# EcobitNRF9160_EV2.net
KiCad netlist of a schematic drawn in EAGLE
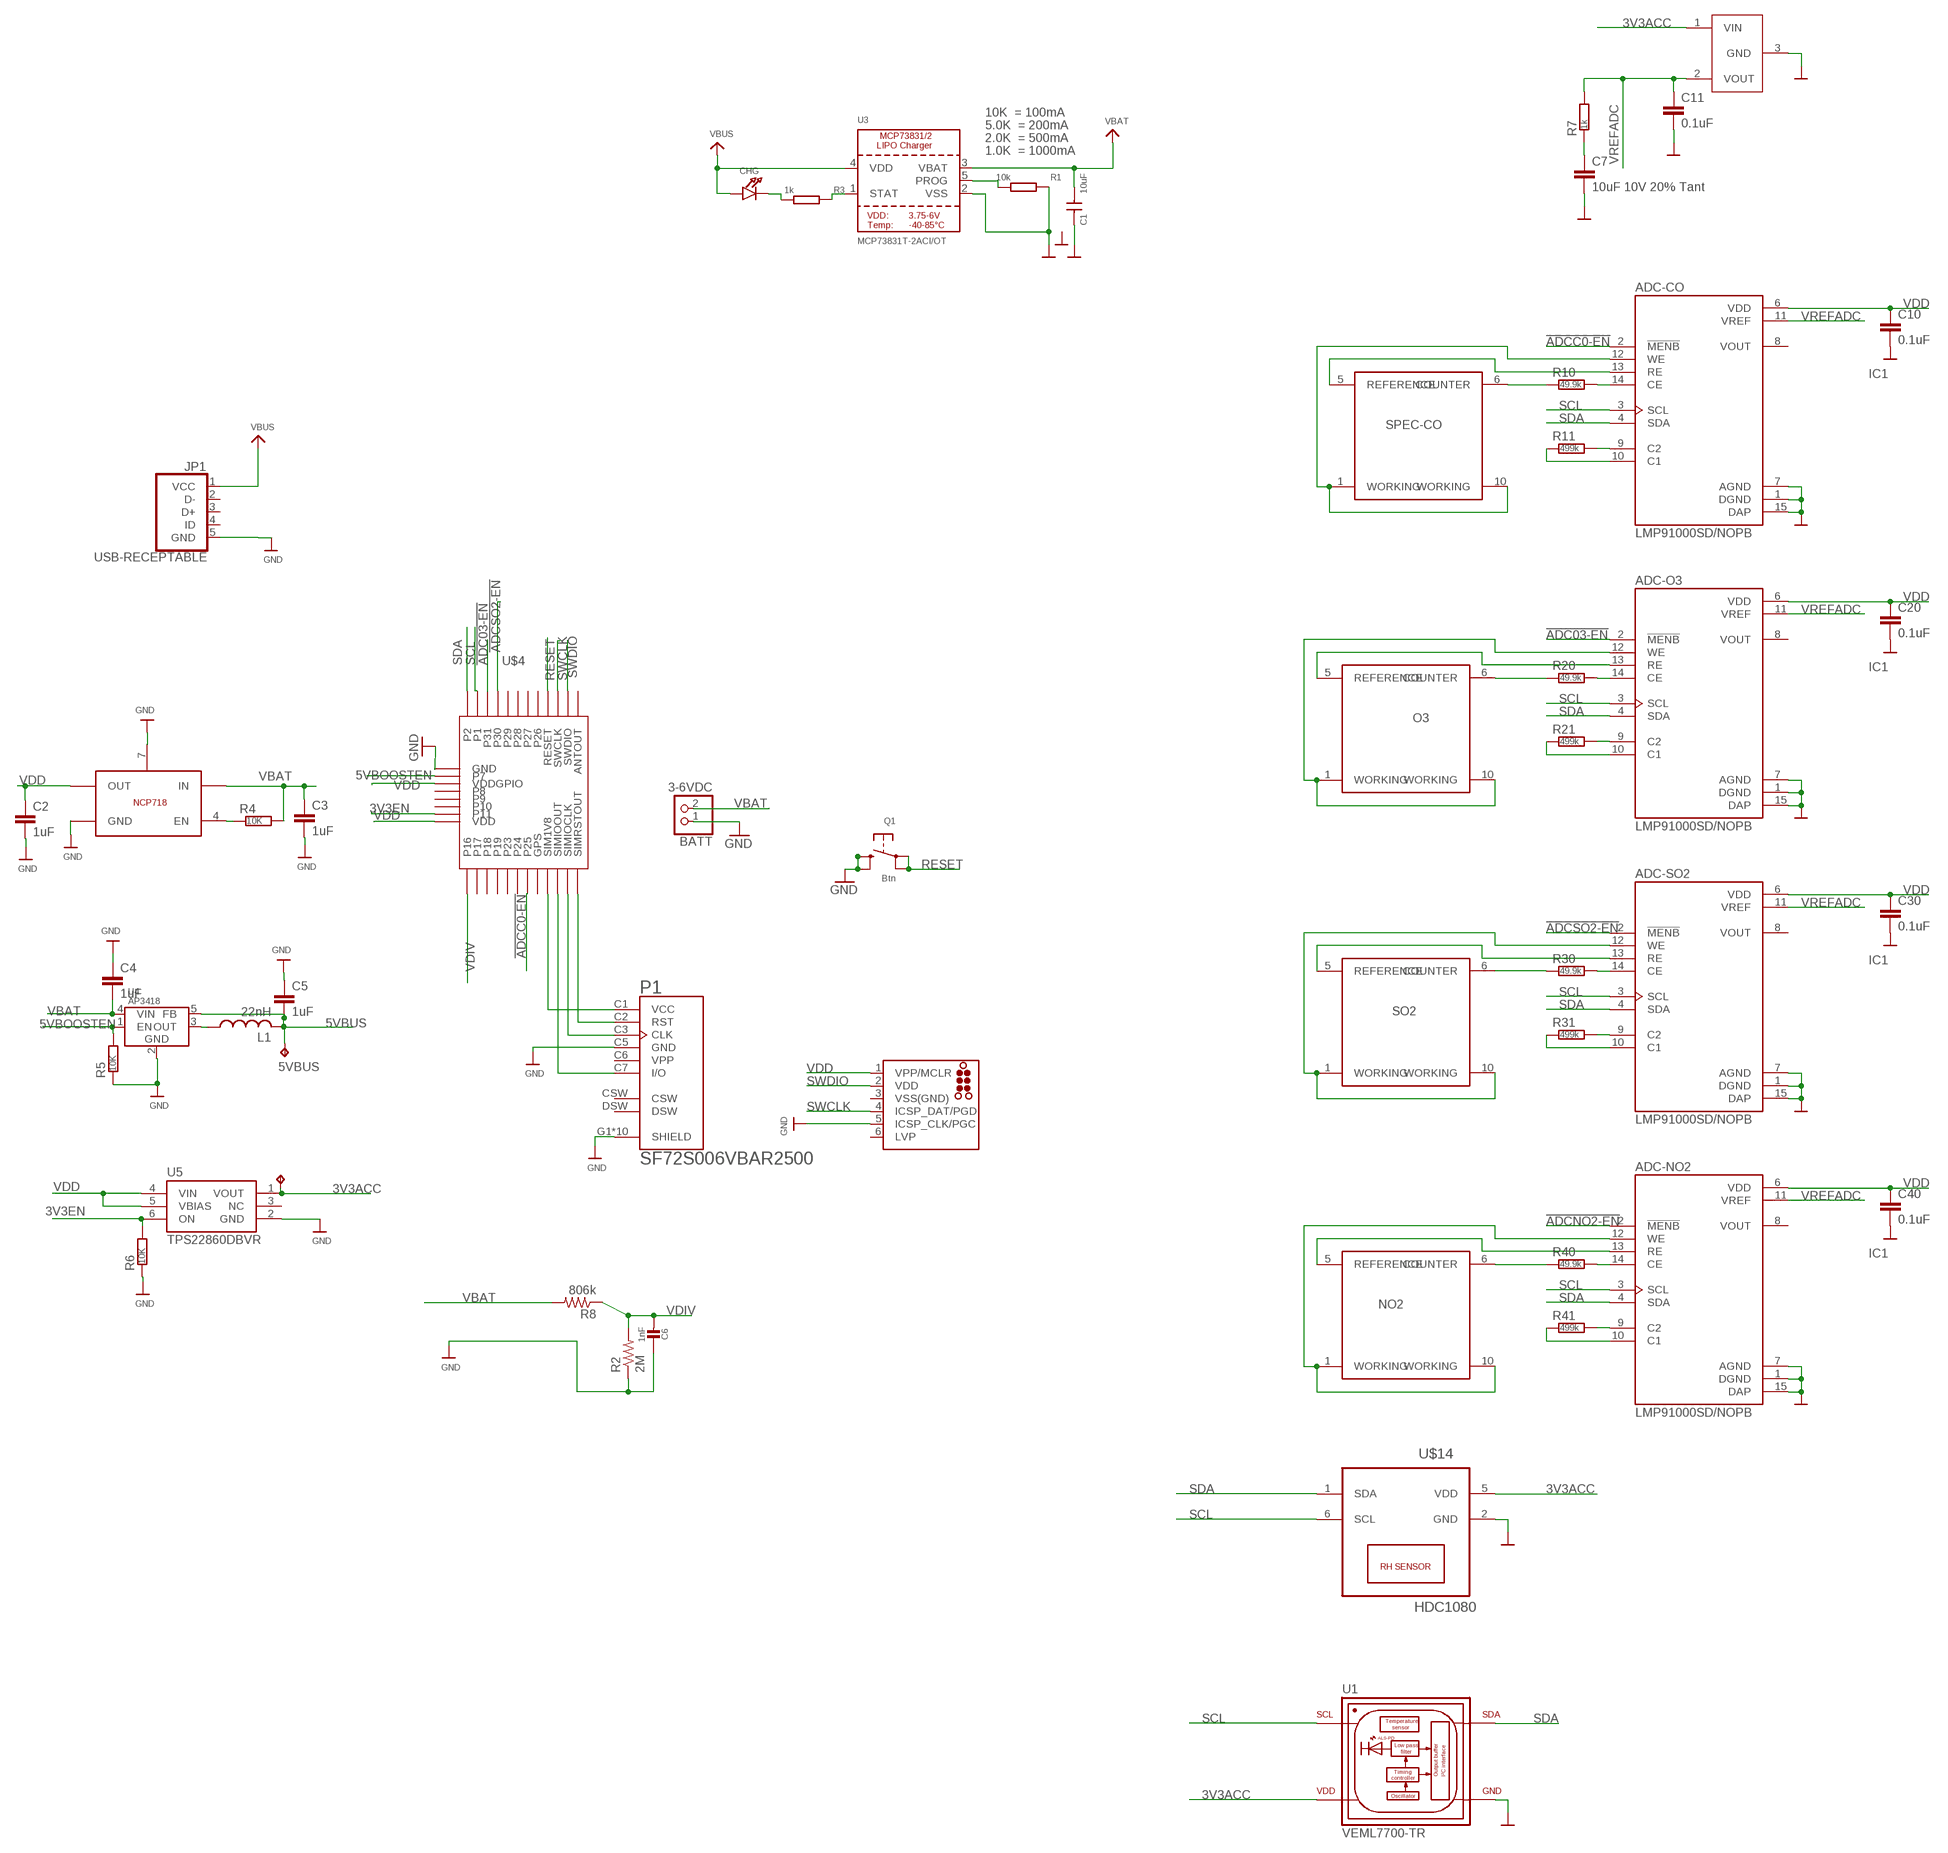
[diagram p0: schematic, sheet 1]

(export (version "E")
  (design (tool "Eeschema 10.0.6"))
  (components
    (comp (ref "5VBUS")
      (value "TPTP15R")
      (footprint "eagle-import:TP15R")
      (libsource (lib "eagle-import") (part "TPTP15R"))
    )
    (comp (ref "5VBUS1")
      (value "TPTP15R")
      (footprint "eagle-import:TP15R")
      (libsource (lib "eagle-import") (part "TPTP15R"))
    )
    (comp (ref "ADC-CO")
      (value "LMP91000SD/NOPB")
      (footprint "eagle-import:SON50P400X400X80-15N")
      (fields (field (name "MF") "Texas Instruments"))
      (libsource (lib "eagle-import") (part "LMP91000SD/NOPB"))
    )
    (comp (ref "ADC-NO2")
      (value "LMP91000SD/NOPB")
      (footprint "eagle-import:SON50P400X400X80-15N")
      (fields (field (name "MF") "Texas Instruments"))
      (libsource (lib "eagle-import") (part "LMP91000SD/NOPB"))
    )
    (comp (ref "ADC-O3")
      (value "LMP91000SD/NOPB")
      (footprint "eagle-import:SON50P400X400X80-15N")
      (fields (field (name "MF") "Texas Instruments"))
      (libsource (lib "eagle-import") (part "LMP91000SD/NOPB"))
    )
    (comp (ref "ADC-SO2")
      (value "LMP91000SD/NOPB")
      (footprint "eagle-import:SON50P400X400X80-15N")
      (fields (field (name "MF") "Texas Instruments"))
      (libsource (lib "eagle-import") (part "LMP91000SD/NOPB"))
    )
    (comp (ref "BATT")
      (value "3-6VDC")
      (footprint "eagle-import:JSTPH2")
      (libsource (lib "eagle-import") (part "CON_JST_PH_2PIN"))
    )
    (comp (ref "C1")
      (value "10uF")
      (footprint "eagle-import:C-0402")
      (libsource (lib "eagle-import") (part "CAP0402"))
    )
    (comp (ref "C2")
      (value "1uF")
      (footprint "eagle-import:RESC0402_N")
      (libsource (lib "eagle-import") (part "CAPACITOR_0402_N"))
    )
    (comp (ref "C3")
      (value "1uF")
      (footprint "eagle-import:RESC0402_N")
      (libsource (lib "eagle-import") (part "CAPACITOR_0402_N"))
    )
    (comp (ref "C4")
      (value "1uF")
      (footprint "eagle-import:RESC0402_N")
      (libsource (lib "eagle-import") (part "CAPACITOR_0402_N"))
    )
    (comp (ref "C5")
      (value "1uF")
      (footprint "eagle-import:RESC0402_N")
      (libsource (lib "eagle-import") (part "CAPACITOR_0402_N"))
    )
    (comp (ref "C6")
      (value "1nF")
      (footprint "eagle-import:0603-NO")
      (libsource (lib "eagle-import") (part "CAP_CERAMIC0603_NO"))
    )
    (comp (ref "C7")
      (value "10uF 10V 20% Tant")
      (footprint "eagle-import:RESC0805_N")
      (libsource (lib "eagle-import") (part "CAPACITOR_0805_N"))
    )
    (comp (ref "C10")
      (value "0.1uF")
      (footprint "eagle-import:RESC0603_N")
      (libsource (lib "eagle-import") (part "CAPACITOR_0603_N"))
    )
    (comp (ref "C11")
      (value "0.1uF")
      (footprint "eagle-import:RESC0603_N")
      (libsource (lib "eagle-import") (part "CAPACITOR_0603_N"))
    )
    (comp (ref "C20")
      (value "0.1uF")
      (footprint "eagle-import:RESC0603_N")
      (libsource (lib "eagle-import") (part "CAPACITOR_0603_N"))
    )
    (comp (ref "C30")
      (value "0.1uF")
      (footprint "eagle-import:RESC0603_N")
      (libsource (lib "eagle-import") (part "CAPACITOR_0603_N"))
    )
    (comp (ref "C40")
      (value "0.1uF")
      (footprint "eagle-import:RESC0603_N")
      (libsource (lib "eagle-import") (part "CAPACITOR_0603_N"))
    )
    (comp (ref "CHG")
      (value "LED0805_NOOUTLINE")
      (footprint "eagle-import:CHIPLED_0805_NOOUTLINE")
      (libsource (lib "eagle-import") (part "LED0805_NOOUTLINE"))
    )
    (comp (ref "IC1")
      (value "ISL60002DIH320Z-TK")
      (footprint "eagle-import:SOT-23-3")
      (libsource (lib "eagle-import") (part "ISL60002DIH320Z-TK"))
    )
    (comp (ref "J2")
      (value "TC2030-MCP-NL")
      (footprint "eagle-import:TC2030-MCP-NL")
      (libsource (lib "eagle-import") (part "TC2030-MCP-NL"))
    )
    (comp (ref "JP1")
      (value "USB-RECEPTABLE")
      (footprint "eagle-import:FCI-10103594-0001LF")
      (libsource (lib "eagle-import") (part "USB-RECEPTABLE"))
    )
    (comp (ref "L1")
      (value "22nH")
      (footprint "eagle-import:RESC0603_N")
      (libsource (lib "eagle-import") (part "INDUCTOR_0603_N"))
    )
    (comp (ref "NO2")
      (value "SPECSENSOR")
      (footprint "eagle-import:SPECSENSOR")
      (libsource (lib "eagle-import") (part "SPECSENSOR"))
    )
    (comp (ref "O3")
      (value "SPECSENSOR")
      (footprint "eagle-import:SPECSENSOR")
      (libsource (lib "eagle-import") (part "SPECSENSOR"))
    )
    (comp (ref "P1")
      (value "SF72S006VBAR2500")
      (footprint "eagle-import:JAE_SF72S006VBAR2500")
      (fields (field (name "MF") "JAE Electronics"))
      (libsource (lib "eagle-import") (part "SF72S006VBAR2500"))
    )
    (comp (ref "Q1")
      (value "Btn")
      (footprint "eagle-import:BTN_KMR2_4.6X2.8")
      (libsource (lib "eagle-import") (part "SWITCH_TACT_SMT4.6X2.8"))
    )
    (comp (ref "R1")
      (value "10k")
      (footprint "eagle-import:R0402")
      (libsource (lib "eagle-import") (part "RESR0402"))
    )
    (comp (ref "R2")
      (value "2M")
      (footprint "eagle-import:R0603")
      (libsource (lib "eagle-import") (part "R-US_R0603"))
    )
    (comp (ref "R3")
      (value "1k")
      (footprint "eagle-import:R0402")
      (libsource (lib "eagle-import") (part "RESR0402"))
    )
    (comp (ref "R4")
      (value "10K")
      (footprint "eagle-import:RESC0402_N")
      (libsource (lib "eagle-import") (part "RESISTOR_0402_N"))
    )
    (comp (ref "R5")
      (value "10K")
      (footprint "eagle-import:RESC0402_N")
      (libsource (lib "eagle-import") (part "RESISTOR_0402_N"))
    )
    (comp (ref "R6")
      (value "10K")
      (footprint "eagle-import:RESC0402_N")
      (libsource (lib "eagle-import") (part "RESISTOR_0402_N"))
    )
    (comp (ref "R7")
      (value "1k")
      (footprint "eagle-import:RESC0603_N")
      (libsource (lib "eagle-import") (part "RESISTOR_0603_N"))
    )
    (comp (ref "R8")
      (value "806k")
      (footprint "eagle-import:R0603")
      (libsource (lib "eagle-import") (part "R-US_R0603"))
    )
    (comp (ref "R10")
      (value "49.9k")
      (footprint "eagle-import:RESC0603_N")
      (libsource (lib "eagle-import") (part "RESISTOR_0603_N"))
    )
    (comp (ref "R11")
      (value "499k")
      (footprint "eagle-import:RESC0603_N")
      (libsource (lib "eagle-import") (part "RESISTOR_0603_N"))
    )
    (comp (ref "R20")
      (value "49.9k")
      (footprint "eagle-import:RESC0603_N")
      (libsource (lib "eagle-import") (part "RESISTOR_0603_N"))
    )
    (comp (ref "R21")
      (value "499k")
      (footprint "eagle-import:RESC0603_N")
      (libsource (lib "eagle-import") (part "RESISTOR_0603_N"))
    )
    (comp (ref "R30")
      (value "49.9k")
      (footprint "eagle-import:RESC0603_N")
      (libsource (lib "eagle-import") (part "RESISTOR_0603_N"))
    )
    (comp (ref "R31")
      (value "499k")
      (footprint "eagle-import:RESC0603_N")
      (libsource (lib "eagle-import") (part "RESISTOR_0603_N"))
    )
    (comp (ref "R40")
      (value "49.9k")
      (footprint "eagle-import:RESC0603_N")
      (libsource (lib "eagle-import") (part "RESISTOR_0603_N"))
    )
    (comp (ref "R41")
      (value "499k")
      (footprint "eagle-import:RESC0603_N")
      (libsource (lib "eagle-import") (part "RESISTOR_0603_N"))
    )
    (comp (ref "SO2")
      (value "SPECSENSOR")
      (footprint "eagle-import:SPECSENSOR")
      (libsource (lib "eagle-import") (part "SPECSENSOR"))
    )
    (comp (ref "SPEC-CO")
      (value "SPECSENSOR")
      (footprint "eagle-import:SPECSENSOR")
      (libsource (lib "eagle-import") (part "SPECSENSOR"))
    )
    (comp (ref "U$4")
      (value "NRF9160MODULE")
      (footprint "eagle-import:NRF9160MODULE")
      (libsource (lib "eagle-import") (part "NRF9160MODULE"))
    )
    (comp (ref "U$14")
      (value "HDC1080")
      (footprint "eagle-import:TI-S-PWSON-N6")
      (libsource (lib "eagle-import") (part "HDC1080"))
    )
    (comp (ref "U1")
      (value "VEML7700-TR")
      (footprint "eagle-import:XDCR_VEML7700-TR")
      (fields (field (name "DIGI-KEY_PART_NUMBER") "VEML7700CT-ND") (field (name "MF") "Vishay"))
      (libsource (lib "eagle-import") (part "VEML7700-TR"))
    )
    (comp (ref "U2")
      (value "NCP718")
      (footprint "eagle-import:NCP718-WDFN6")
      (libsource (lib "eagle-import") (part "NCP718"))
    )
    (comp (ref "U3")
      (value "MCP73831T-2ACI/OT")
      (footprint "eagle-import:SOT23-5")
      (libsource (lib "eagle-import") (part "MCP73831/2"))
    )
    (comp (ref "U4")
      (value "AP3418")
      (footprint "eagle-import:SOT25")
      (libsource (lib "eagle-import") (part "AP3418"))
    )
    (comp (ref "U5")
      (value "TPS22860DBVR")
      (footprint "eagle-import:R-PDSO-G6")
      (libsource (lib "eagle-import") (part "TPS22860DBVR"))
    )
  )
  (nets
    (net (code "1") (name "/3V3ACC") (class "Default")
      (node (ref "5VBUS1") (pin "TP") (pinfunction "TP_TP") (pintype "input"))
      (node (ref "IC1") (pin "1") (pinfunction "VIN_1") (pintype "power_in"))
      (node (ref "U$14") (pin "5") (pinfunction "VDD_5") (pintype "output"))
      (node (ref "U1") (pin "2") (pinfunction "VDD_2") (pintype "power_in"))
      (node (ref "U5") (pin "1") (pinfunction "VOUT_1") (pintype "power_in"))
    )
    (net (code "2") (name "/3V3EN") (class "Default")
      (node (ref "R6") (pin "2") (pinfunction "2_2") (pintype "passive"))
      (node (ref "U$4") (pin "P11") (pinfunction "P11_P11") (pintype "bidirectional"))
      (node (ref "U5") (pin "6") (pinfunction "ON_6") (pintype "input"))
    )
    (net (code "3") (name "/5VBOOSTEN") (class "Default")
      (node (ref "R5") (pin "2") (pinfunction "2_2") (pintype "passive"))
      (node (ref "U$4") (pin "P7") (pinfunction "P7_P7") (pintype "bidirectional"))
      (node (ref "U4") (pin "1") (pinfunction "EN_1") (pintype "bidirectional"))
    )
    (net (code "4") (name "/5VBUS") (class "Default")
      (node (ref "5VBUS") (pin "TP") (pinfunction "TP_TP") (pintype "input"))
      (node (ref "C5") (pin "2") (pinfunction "2_2") (pintype "passive"))
      (node (ref "L1") (pin "2") (pinfunction "2_2") (pintype "passive"))
      (node (ref "U4") (pin "5") (pinfunction "FB_5") (pintype "bidirectional"))
    )
    (net (code "8") (name "/RESET") (class "Default")
      (node (ref "Q1") (pin "A") (pinfunction "P_A") (pintype "passive"))
      (node (ref "Q1") (pin "A'") (pinfunction "P1_A'") (pintype "passive"))
      (node (ref "U$4") (pin "RESET") (pinfunction "RESET_RESET") (pintype "bidirectional"))
    )
    (net (code "9") (name "/SCL") (class "Default")
      (node (ref "ADC-CO") (pin "3") (pinfunction "SCL_3") (pintype "input"))
      (node (ref "ADC-NO2") (pin "3") (pinfunction "SCL_3") (pintype "input"))
      (node (ref "ADC-O3") (pin "3") (pinfunction "SCL_3") (pintype "input"))
      (node (ref "ADC-SO2") (pin "3") (pinfunction "SCL_3") (pintype "input"))
      (node (ref "U$14") (pin "6") (pinfunction "SCL_6") (pintype "passive"))
      (node (ref "U$4") (pin "P1") (pinfunction "P1_P1") (pintype "bidirectional"))
      (node (ref "U1") (pin "1") (pinfunction "SCL_1") (pintype "input"))
    )
    (net (code "10") (name "/SDA") (class "Default")
      (node (ref "ADC-CO") (pin "4") (pinfunction "SDA_4") (pintype "bidirectional"))
      (node (ref "ADC-NO2") (pin "4") (pinfunction "SDA_4") (pintype "bidirectional"))
      (node (ref "ADC-O3") (pin "4") (pinfunction "SDA_4") (pintype "bidirectional"))
      (node (ref "ADC-SO2") (pin "4") (pinfunction "SDA_4") (pintype "bidirectional"))
      (node (ref "U$14") (pin "1") (pinfunction "SDA_1") (pintype "power_in"))
      (node (ref "U$4") (pin "P2") (pinfunction "P2_P2") (pintype "bidirectional"))
      (node (ref "U1") (pin "4") (pinfunction "SDA_4") (pintype "bidirectional"))
    )
    (net (code "13") (name "/SWCLK") (class "Default")
      (node (ref "J2") (pin "4") (pinfunction "ICSP_DAT/PGD_4") (pintype "bidirectional"))
      (node (ref "U$4") (pin "SWCLK") (pinfunction "SWCLK_SWCLK") (pintype "bidirectional"))
    )
    (net (code "14") (name "/SWDIO") (class "Default")
      (node (ref "J2") (pin "2") (pinfunction "VDD_2") (pintype "power_in"))
      (node (ref "U$4") (pin "SWDIO") (pinfunction "SWDIO_SWDIO") (pintype "bidirectional"))
    )
    (net (code "15") (name "/VDD") (class "Default")
      (node (ref "ADC-CO") (pin "6") (pinfunction "VDD_6") (pintype "power_in"))
      (node (ref "ADC-NO2") (pin "6") (pinfunction "VDD_6") (pintype "power_in"))
      (node (ref "ADC-O3") (pin "6") (pinfunction "VDD_6") (pintype "power_in"))
      (node (ref "ADC-SO2") (pin "6") (pinfunction "VDD_6") (pintype "power_in"))
      (node (ref "C10") (pin "1") (pinfunction "1_1") (pintype "passive"))
      (node (ref "C2") (pin "1") (pinfunction "1_1") (pintype "passive"))
      (node (ref "C20") (pin "1") (pinfunction "1_1") (pintype "passive"))
      (node (ref "C30") (pin "1") (pinfunction "1_1") (pintype "passive"))
      (node (ref "C40") (pin "1") (pinfunction "1_1") (pintype "passive"))
      (node (ref "J2") (pin "1") (pinfunction "VPP/MCLR_1") (pintype "passive"))
      (node (ref "U$4") (pin "VDD") (pinfunction "VDD_VDD") (pintype "bidirectional"))
      (node (ref "U$4") (pin "VDDGPIO") (pinfunction "VDDGPIO_VDDGPIO") (pintype "bidirectional"))
      (node (ref "U2") (pin "1") (pinfunction "OUT_1") (pintype "power_in"))
      (node (ref "U5") (pin "4") (pinfunction "VIN_4") (pintype "power_in"))
      (node (ref "U5") (pin "5") (pinfunction "VBIAS_5") (pintype "power_in"))
    )
    (net (code "16") (name "/VDIV") (class "Default")
      (node (ref "C6") (pin "2") (pinfunction "2_2") (pintype "passive"))
      (node (ref "R2") (pin "2") (pinfunction "2_2") (pintype "passive"))
      (node (ref "R8") (pin "1") (pinfunction "1_1") (pintype "passive"))
      (node (ref "U$4") (pin "P16") (pinfunction "P16_P16") (pintype "bidirectional"))
    )
    (net (code "17") (name "/VPP") (class "Default")
      (node (ref "P1") (pin "C6") (pinfunction "VPP_C6") (pintype "power_in"))
    )
    (net (code "18") (name "/VREFADC") (class "Default")
      (node (ref "ADC-CO") (pin "11") (pinfunction "VREF_11") (pintype "power_in"))
      (node (ref "ADC-NO2") (pin "11") (pinfunction "VREF_11") (pintype "power_in"))
      (node (ref "ADC-O3") (pin "11") (pinfunction "VREF_11") (pintype "power_in"))
      (node (ref "ADC-SO2") (pin "11") (pinfunction "VREF_11") (pintype "power_in"))
      (node (ref "C11") (pin "1") (pinfunction "1_1") (pintype "passive"))
      (node (ref "IC1") (pin "2") (pinfunction "VOUT_2") (pintype "power_in"))
      (node (ref "R7") (pin "2") (pinfunction "2_2") (pintype "passive"))
    )
    (net (code "19") (name "/VSS(GND)") (class "Default")
      (node (ref "J2") (pin "3") (pinfunction "VSS(GND)_3") (pintype "power_in"))
    )
    (net (code "20") (name "/~{ADC03-EN}") (class "Default")
      (node (ref "ADC-O3") (pin "2") (pinfunction "~{MENB}_2") (pintype "input"))
      (node (ref "U$4") (pin "P31") (pinfunction "P31_P31") (pintype "bidirectional"))
    )
    (net (code "21") (name "/~{ADCC0-EN}") (class "Default")
      (node (ref "ADC-CO") (pin "2") (pinfunction "~{MENB}_2") (pintype "input"))
      (node (ref "U$4") (pin "P25") (pinfunction "P25_P25") (pintype "bidirectional"))
    )
    (net (code "22") (name "/~{ADCNO2-EN}") (class "Default")
      (node (ref "ADC-NO2") (pin "2") (pinfunction "~{MENB}_2") (pintype "input"))
    )
    (net (code "23") (name "/~{ADCSO2-EN}") (class "Default")
      (node (ref "ADC-SO2") (pin "2") (pinfunction "~{MENB}_2") (pintype "input"))
      (node (ref "U$4") (pin "P30") (pinfunction "P30_P30") (pintype "bidirectional"))
    )
    (net (code "24") (name "GND") (class "Default")
      (node (ref "ADC-CO") (pin "1") (pinfunction "DGND_1") (pintype "power_in"))
      (node (ref "ADC-CO") (pin "15") (pinfunction "DAP_15") (pintype "power_in"))
      (node (ref "ADC-CO") (pin "7") (pinfunction "AGND_7") (pintype "power_in"))
      (node (ref "ADC-NO2") (pin "1") (pinfunction "DGND_1") (pintype "power_in"))
      (node (ref "ADC-NO2") (pin "15") (pinfunction "DAP_15") (pintype "power_in"))
      (node (ref "ADC-NO2") (pin "7") (pinfunction "AGND_7") (pintype "power_in"))
      (node (ref "ADC-O3") (pin "1") (pinfunction "DGND_1") (pintype "power_in"))
      (node (ref "ADC-O3") (pin "15") (pinfunction "DAP_15") (pintype "power_in"))
      (node (ref "ADC-O3") (pin "7") (pinfunction "AGND_7") (pintype "power_in"))
      (node (ref "ADC-SO2") (pin "1") (pinfunction "DGND_1") (pintype "power_in"))
      (node (ref "ADC-SO2") (pin "15") (pinfunction "DAP_15") (pintype "power_in"))
      (node (ref "ADC-SO2") (pin "7") (pinfunction "AGND_7") (pintype "power_in"))
      (node (ref "BATT") (pin "1") (pinfunction "1_1") (pintype "passive"))
      (node (ref "C1") (pin "2") (pinfunction "2_2") (pintype "bidirectional"))
      (node (ref "C10") (pin "2") (pinfunction "2_2") (pintype "passive"))
      (node (ref "C11") (pin "2") (pinfunction "2_2") (pintype "passive"))
      (node (ref "C2") (pin "2") (pinfunction "2_2") (pintype "passive"))
      (node (ref "C20") (pin "2") (pinfunction "2_2") (pintype "passive"))
      (node (ref "C3") (pin "2") (pinfunction "2_2") (pintype "passive"))
      (node (ref "C30") (pin "2") (pinfunction "2_2") (pintype "passive"))
      (node (ref "C4") (pin "1") (pinfunction "1_1") (pintype "passive"))
      (node (ref "C40") (pin "2") (pinfunction "2_2") (pintype "passive"))
      (node (ref "C5") (pin "1") (pinfunction "1_1") (pintype "passive"))
      (node (ref "C6") (pin "1") (pinfunction "1_1") (pintype "passive"))
      (node (ref "C7") (pin "2") (pinfunction "2_2") (pintype "passive"))
      (node (ref "IC1") (pin "3") (pinfunction "GND_3") (pintype "power_in"))
      (node (ref "J2") (pin "5") (pinfunction "ICSP_CLK/PGC_5") (pintype "output"))
      (node (ref "JP1") (pin "5") (pinfunction "GND_5") (pintype "bidirectional"))
      (node (ref "P1") (pin "C5") (pinfunction "GND_C5") (pintype "power_in"))
      (node (ref "P1") (pin "G1") (pinfunction "SHIELD_G1") (pintype "passive"))
      (node (ref "P1") (pin "G10") (pinfunction "SHIELD_G10") (pintype "passive"))
      (node (ref "P1") (pin "G2") (pinfunction "SHIELD_G2") (pintype "passive"))
      (node (ref "P1") (pin "G3") (pinfunction "SHIELD_G3") (pintype "passive"))
      (node (ref "P1") (pin "G4") (pinfunction "SHIELD_G4") (pintype "passive"))
      (node (ref "P1") (pin "G5") (pinfunction "SHIELD_G5") (pintype "passive"))
      (node (ref "P1") (pin "G6") (pinfunction "SHIELD_G6") (pintype "passive"))
      (node (ref "P1") (pin "G7") (pinfunction "SHIELD_G7") (pintype "passive"))
      (node (ref "P1") (pin "G8") (pinfunction "SHIELD_G8") (pintype "passive"))
      (node (ref "P1") (pin "G9") (pinfunction "SHIELD_G9") (pintype "passive"))
      (node (ref "Q1") (pin "B") (pinfunction "S_B") (pintype "passive"))
      (node (ref "Q1") (pin "B'") (pinfunction "S1_B'") (pintype "passive"))
      (node (ref "R1") (pin "1") (pinfunction "1_1") (pintype "bidirectional"))
      (node (ref "R2") (pin "1") (pinfunction "1_1") (pintype "passive"))
      (node (ref "R5") (pin "1") (pinfunction "1_1") (pintype "passive"))
      (node (ref "R6") (pin "1") (pinfunction "1_1") (pintype "passive"))
      (node (ref "U$14") (pin "2") (pinfunction "GND_2") (pintype "passive"))
      (node (ref "U$4") (pin "GND") (pinfunction "GND_GND") (pintype "bidirectional"))
      (node (ref "U1") (pin "3") (pinfunction "GND_3") (pintype "power_in"))
      (node (ref "U2") (pin "3") (pinfunction "GND_3") (pintype "power_in"))
      (node (ref "U2") (pin "7") (pinfunction "GND_7") (pintype "power_in"))
      (node (ref "U3") (pin "2") (pinfunction "VSS_2") (pintype "power_in"))
      (node (ref "U4") (pin "2") (pinfunction "GND_2") (pintype "bidirectional"))
      (node (ref "U5") (pin "2") (pinfunction "GND_2") (pintype "power_in"))
    )
    (net (code "25") (name "Net-(ADC-CO-C1)") (class "Default")
      (node (ref "ADC-CO") (pin "10") (pinfunction "C1_10") (pintype "passive"))
      (node (ref "R11") (pin "1") (pinfunction "1_1") (pintype "passive"))
    )
    (net (code "26") (name "Net-(ADC-CO-C2)") (class "Default")
      (node (ref "ADC-CO") (pin "9") (pinfunction "C2_9") (pintype "passive"))
      (node (ref "R11") (pin "2") (pinfunction "2_2") (pintype "passive"))
    )
    (net (code "27") (name "Net-(ADC-CO-CE)") (class "Default")
      (node (ref "ADC-CO") (pin "14") (pinfunction "CE_14") (pintype "input"))
      (node (ref "R10") (pin "2") (pinfunction "2_2") (pintype "passive"))
    )
    (net (code "28") (name "Net-(ADC-CO-RE)") (class "Default")
      (node (ref "ADC-CO") (pin "13") (pinfunction "RE_13") (pintype "input"))
      (node (ref "SPEC-CO") (pin "5") (pinfunction "REFERENCE_5") (pintype "bidirectional"))
    )
    (net (code "29") (name "Net-(ADC-CO-WE)") (class "Default")
      (node (ref "ADC-CO") (pin "12") (pinfunction "WE_12") (pintype "input"))
      (node (ref "SPEC-CO") (pin "1") (pinfunction "WORKING_1") (pintype "bidirectional"))
      (node (ref "SPEC-CO") (pin "10") (pinfunction "WORKING_10") (pintype "bidirectional"))
    )
    (net (code "30") (name "Net-(ADC-NO2-C1)") (class "Default")
      (node (ref "ADC-NO2") (pin "10") (pinfunction "C1_10") (pintype "passive"))
      (node (ref "R41") (pin "1") (pinfunction "1_1") (pintype "passive"))
    )
    (net (code "31") (name "Net-(ADC-NO2-C2)") (class "Default")
      (node (ref "ADC-NO2") (pin "9") (pinfunction "C2_9") (pintype "passive"))
      (node (ref "R41") (pin "2") (pinfunction "2_2") (pintype "passive"))
    )
    (net (code "32") (name "Net-(ADC-NO2-CE)") (class "Default")
      (node (ref "ADC-NO2") (pin "14") (pinfunction "CE_14") (pintype "input"))
      (node (ref "R40") (pin "2") (pinfunction "2_2") (pintype "passive"))
    )
    (net (code "33") (name "Net-(ADC-NO2-RE)") (class "Default")
      (node (ref "ADC-NO2") (pin "13") (pinfunction "RE_13") (pintype "input"))
      (node (ref "NO2") (pin "5") (pinfunction "REFERENCE_5") (pintype "bidirectional"))
    )
    (net (code "34") (name "Net-(ADC-NO2-WE)") (class "Default")
      (node (ref "ADC-NO2") (pin "12") (pinfunction "WE_12") (pintype "input"))
      (node (ref "NO2") (pin "1") (pinfunction "WORKING_1") (pintype "bidirectional"))
      (node (ref "NO2") (pin "10") (pinfunction "WORKING_10") (pintype "bidirectional"))
    )
    (net (code "35") (name "Net-(ADC-O3-C1)") (class "Default")
      (node (ref "ADC-O3") (pin "10") (pinfunction "C1_10") (pintype "passive"))
      (node (ref "R21") (pin "1") (pinfunction "1_1") (pintype "passive"))
    )
    (net (code "36") (name "Net-(ADC-O3-C2)") (class "Default")
      (node (ref "ADC-O3") (pin "9") (pinfunction "C2_9") (pintype "passive"))
      (node (ref "R21") (pin "2") (pinfunction "2_2") (pintype "passive"))
    )
    (net (code "37") (name "Net-(ADC-O3-CE)") (class "Default")
      (node (ref "ADC-O3") (pin "14") (pinfunction "CE_14") (pintype "input"))
      (node (ref "R20") (pin "2") (pinfunction "2_2") (pintype "passive"))
    )
    (net (code "38") (name "Net-(ADC-O3-RE)") (class "Default")
      (node (ref "ADC-O3") (pin "13") (pinfunction "RE_13") (pintype "input"))
      (node (ref "O3") (pin "5") (pinfunction "REFERENCE_5") (pintype "bidirectional"))
    )
    (net (code "39") (name "Net-(ADC-O3-WE)") (class "Default")
      (node (ref "ADC-O3") (pin "12") (pinfunction "WE_12") (pintype "input"))
      (node (ref "O3") (pin "1") (pinfunction "WORKING_1") (pintype "bidirectional"))
      (node (ref "O3") (pin "10") (pinfunction "WORKING_10") (pintype "bidirectional"))
    )
    (net (code "40") (name "Net-(ADC-SO2-C1)") (class "Default")
      (node (ref "ADC-SO2") (pin "10") (pinfunction "C1_10") (pintype "passive"))
      (node (ref "R31") (pin "1") (pinfunction "1_1") (pintype "passive"))
    )
    (net (code "41") (name "Net-(ADC-SO2-C2)") (class "Default")
      (node (ref "ADC-SO2") (pin "9") (pinfunction "C2_9") (pintype "passive"))
      (node (ref "R31") (pin "2") (pinfunction "2_2") (pintype "passive"))
    )
    (net (code "42") (name "Net-(ADC-SO2-CE)") (class "Default")
      (node (ref "ADC-SO2") (pin "14") (pinfunction "CE_14") (pintype "input"))
      (node (ref "R30") (pin "2") (pinfunction "2_2") (pintype "passive"))
    )
    (net (code "43") (name "Net-(ADC-SO2-RE)") (class "Default")
      (node (ref "ADC-SO2") (pin "13") (pinfunction "RE_13") (pintype "input"))
      (node (ref "SO2") (pin "5") (pinfunction "REFERENCE_5") (pintype "bidirectional"))
    )
    (net (code "44") (name "Net-(ADC-SO2-WE)") (class "Default")
      (node (ref "ADC-SO2") (pin "12") (pinfunction "WE_12") (pintype "input"))
      (node (ref "SO2") (pin "1") (pinfunction "WORKING_1") (pintype "bidirectional"))
      (node (ref "SO2") (pin "10") (pinfunction "WORKING_10") (pintype "bidirectional"))
    )
    (net (code "45") (name "Net-(C7-Pad1)") (class "Default")
      (node (ref "C7") (pin "1") (pinfunction "1_1") (pintype "passive"))
      (node (ref "R7") (pin "1") (pinfunction "1_1") (pintype "passive"))
    )
    (net (code "46") (name "Net-(CHG-PadC)") (class "Default")
      (node (ref "CHG") (pin "C") (pinfunction "C_C") (pintype "passive"))
      (node (ref "R3") (pin "2") (pinfunction "2_2") (pintype "bidirectional"))
    )
    (net (code "47") (name "Net-(NO2-COUNTER)") (class "Default")
      (node (ref "NO2") (pin "6") (pinfunction "COUNTER_6") (pintype "bidirectional"))
      (node (ref "R40") (pin "1") (pinfunction "1_1") (pintype "passive"))
    )
    (net (code "48") (name "Net-(O3-COUNTER)") (class "Default")
      (node (ref "O3") (pin "6") (pinfunction "COUNTER_6") (pintype "bidirectional"))
      (node (ref "R20") (pin "1") (pinfunction "1_1") (pintype "passive"))
    )
    (net (code "49") (name "Net-(P1-CLK)") (class "Default")
      (node (ref "P1") (pin "C3") (pinfunction "CLK_C3") (pintype "bidirectional"))
      (node (ref "U$4") (pin "SIMCLKOUT") (pinfunction "SIMIOCLK_SIMCLKOUT") (pintype "bidirectional"))
    )
    (net (code "50") (name "Net-(P1-I{slash}O)") (class "Default")
      (node (ref "P1") (pin "C7") (pinfunction "I/O_C7") (pintype "bidirectional"))
      (node (ref "U$4") (pin "SIMIOOUT") (pinfunction "SIMIOOUT_SIMIOOUT") (pintype "bidirectional"))
    )
    (net (code "51") (name "Net-(P1-RST)") (class "Default")
      (node (ref "P1") (pin "C2") (pinfunction "RST_C2") (pintype "bidirectional"))
      (node (ref "U$4") (pin "SIMRSTOUT") (pinfunction "SIMRSTOUT_SIMRSTOUT") (pintype "bidirectional"))
    )
    (net (code "52") (name "Net-(P1-VCC)") (class "Default")
      (node (ref "P1") (pin "C1") (pinfunction "VCC_C1") (pintype "power_in"))
      (node (ref "U$4") (pin "SIM1V8") (pinfunction "SIM1V8_SIM1V8") (pintype "bidirectional"))
    )
    (net (code "53") (name "Net-(SO2-COUNTER)") (class "Default")
      (node (ref "R30") (pin "1") (pinfunction "1_1") (pintype "passive"))
      (node (ref "SO2") (pin "6") (pinfunction "COUNTER_6") (pintype "bidirectional"))
    )
    (net (code "54") (name "Net-(SPEC-CO-COUNTER)") (class "Default")
      (node (ref "R10") (pin "1") (pinfunction "1_1") (pintype "passive"))
      (node (ref "SPEC-CO") (pin "6") (pinfunction "COUNTER_6") (pintype "bidirectional"))
    )
    (net (code "55") (name "Net-(U2-EN)") (class "Default")
      (node (ref "R4") (pin "1") (pinfunction "1_1") (pintype "passive"))
      (node (ref "U2") (pin "4") (pinfunction "EN_4") (pintype "bidirectional"))
    )
    (net (code "56") (name "Net-(U3-PROG)") (class "Default")
      (node (ref "R1") (pin "2") (pinfunction "2_2") (pintype "bidirectional"))
      (node (ref "U3") (pin "5") (pinfunction "PROG_5") (pintype "input"))
    )
    (net (code "57") (name "Net-(U3-STAT)") (class "Default")
      (node (ref "R3") (pin "1") (pinfunction "1_1") (pintype "bidirectional"))
      (node (ref "U3") (pin "1") (pinfunction "STAT_1") (pintype "output"))
    )
    (net (code "58") (name "Net-(U4-OUT)") (class "Default")
      (node (ref "L1") (pin "1") (pinfunction "1_1") (pintype "passive"))
      (node (ref "U4") (pin "3") (pinfunction "OUT_3") (pintype "bidirectional"))
    )
    (net (code "59") (name "VBAT") (class "Default")
      (node (ref "BATT") (pin "2") (pinfunction "2_2") (pintype "passive"))
      (node (ref "C1") (pin "1") (pinfunction "1_1") (pintype "bidirectional"))
      (node (ref "C3") (pin "1") (pinfunction "1_1") (pintype "passive"))
      (node (ref "C4") (pin "2") (pinfunction "2_2") (pintype "passive"))
      (node (ref "R4") (pin "2") (pinfunction "2_2") (pintype "passive"))
      (node (ref "R8") (pin "2") (pinfunction "2_2") (pintype "passive"))
      (node (ref "U2") (pin "6") (pinfunction "IN_6") (pintype "power_in"))
      (node (ref "U3") (pin "3") (pinfunction "VBAT_3") (pintype "power_in"))
      (node (ref "U4") (pin "4") (pinfunction "VIN_4") (pintype "bidirectional"))
    )
    (net (code "60") (name "VBUS") (class "Default")
      (node (ref "CHG") (pin "A") (pinfunction "A_A") (pintype "passive"))
      (node (ref "JP1") (pin "1") (pinfunction "VCC_1") (pintype "bidirectional"))
      (node (ref "U3") (pin "4") (pinfunction "VDD_4") (pintype "power_in"))
    )
    (net (code "61") (name "unconnected-(ADC-CO-VOUT-Pad8)") (class "Default")
      (node (ref "ADC-CO") (pin "8") (pinfunction "VOUT_8") (pintype "output"))
    )
    (net (code "62") (name "unconnected-(ADC-NO2-VOUT-Pad8)") (class "Default")
      (node (ref "ADC-NO2") (pin "8") (pinfunction "VOUT_8") (pintype "output"))
    )
    (net (code "63") (name "unconnected-(ADC-O3-VOUT-Pad8)") (class "Default")
      (node (ref "ADC-O3") (pin "8") (pinfunction "VOUT_8") (pintype "output"))
    )
    (net (code "64") (name "unconnected-(ADC-SO2-VOUT-Pad8)") (class "Default")
      (node (ref "ADC-SO2") (pin "8") (pinfunction "VOUT_8") (pintype "output"))
    )
    (net (code "65") (name "unconnected-(J2-LVP-Pad6)") (class "Default")
      (node (ref "J2") (pin "6") (pinfunction "LVP_6") (pintype "bidirectional"))
    )
    (net (code "66") (name "unconnected-(JP1-D+-Pad3)") (class "Default")
      (node (ref "JP1") (pin "3") (pinfunction "D+_3") (pintype "bidirectional"))
    )
    (net (code "67") (name "unconnected-(JP1-D--Pad2)") (class "Default")
      (node (ref "JP1") (pin "2") (pinfunction "D-_2") (pintype "bidirectional"))
    )
    (net (code "68") (name "unconnected-(JP1-ID-Pad4)") (class "Default")
      (node (ref "JP1") (pin "4") (pinfunction "ID_4") (pintype "bidirectional"))
    )
    (net (code "69") (name "unconnected-(P1-PadCSW)") (class "Default")
      (node (ref "P1") (pin "CSW") (pinfunction "CSW_CSW") (pintype "bidirectional"))
    )
    (net (code "70") (name "unconnected-(P1-PadDSW)") (class "Default")
      (node (ref "P1") (pin "DSW") (pinfunction "DSW_DSW") (pintype "bidirectional"))
    )
    (net (code "71") (name "unconnected-(U$4-PadANTOUT)") (class "Default")
      (node (ref "U$4") (pin "ANTOUT") (pinfunction "ANTOUT_ANTOUT") (pintype "bidirectional"))
    )
    (net (code "72") (name "unconnected-(U$4-PadGPS)") (class "Default")
      (node (ref "U$4") (pin "GPS") (pinfunction "GPS_GPS") (pintype "bidirectional"))
    )
    (net (code "73") (name "unconnected-(U$4-PadP8)") (class "Default")
      (node (ref "U$4") (pin "P8") (pinfunction "P8_P8") (pintype "bidirectional"))
    )
    (net (code "74") (name "unconnected-(U$4-PadP9)") (class "Default")
      (node (ref "U$4") (pin "P9") (pinfunction "P9_P9") (pintype "bidirectional"))
    )
    (net (code "75") (name "unconnected-(U$4-PadP10)") (class "Default")
      (node (ref "U$4") (pin "P10") (pinfunction "P10_P10") (pintype "bidirectional"))
    )
    (net (code "76") (name "unconnected-(U$4-PadP17)") (class "Default")
      (node (ref "U$4") (pin "P17") (pinfunction "P17_P17") (pintype "bidirectional"))
    )
    (net (code "77") (name "unconnected-(U$4-PadP18)") (class "Default")
      (node (ref "U$4") (pin "P18") (pinfunction "P18_P18") (pintype "bidirectional"))
    )
    (net (code "78") (name "unconnected-(U$4-PadP19)") (class "Default")
      (node (ref "U$4") (pin "P19") (pinfunction "P19_P19") (pintype "bidirectional"))
    )
    (net (code "79") (name "unconnected-(U$4-PadP23)") (class "Default")
      (node (ref "U$4") (pin "P23") (pinfunction "P23_P23") (pintype "bidirectional"))
    )
    (net (code "80") (name "unconnected-(U$4-PadP24)") (class "Default")
      (node (ref "U$4") (pin "P24") (pinfunction "P24_P24") (pintype "bidirectional"))
    )
    (net (code "81") (name "unconnected-(U$4-PadP26)") (class "Default")
      (node (ref "U$4") (pin "P26") (pinfunction "P26_P26") (pintype "bidirectional"))
    )
    (net (code "82") (name "unconnected-(U$4-PadP27)") (class "Default")
      (node (ref "U$4") (pin "P27") (pinfunction "P27_P27") (pintype "bidirectional"))
    )
    (net (code "83") (name "unconnected-(U$4-PadP28)") (class "Default")
      (node (ref "U$4") (pin "P28") (pinfunction "P28_P28") (pintype "bidirectional"))
    )
    (net (code "84") (name "unconnected-(U$4-PadP29)") (class "Default")
      (node (ref "U$4") (pin "P29") (pinfunction "P29_P29") (pintype "bidirectional"))
    )
    (net (code "85") (name "unconnected-(U5-NC-Pad3)") (class "Default")
      (node (ref "U5") (pin "3") (pinfunction "NC_3") (pintype "no_connect"))
    )
  )
)
